# altimeter.net
KiCad netlist of a schematic drawn in EAGLE
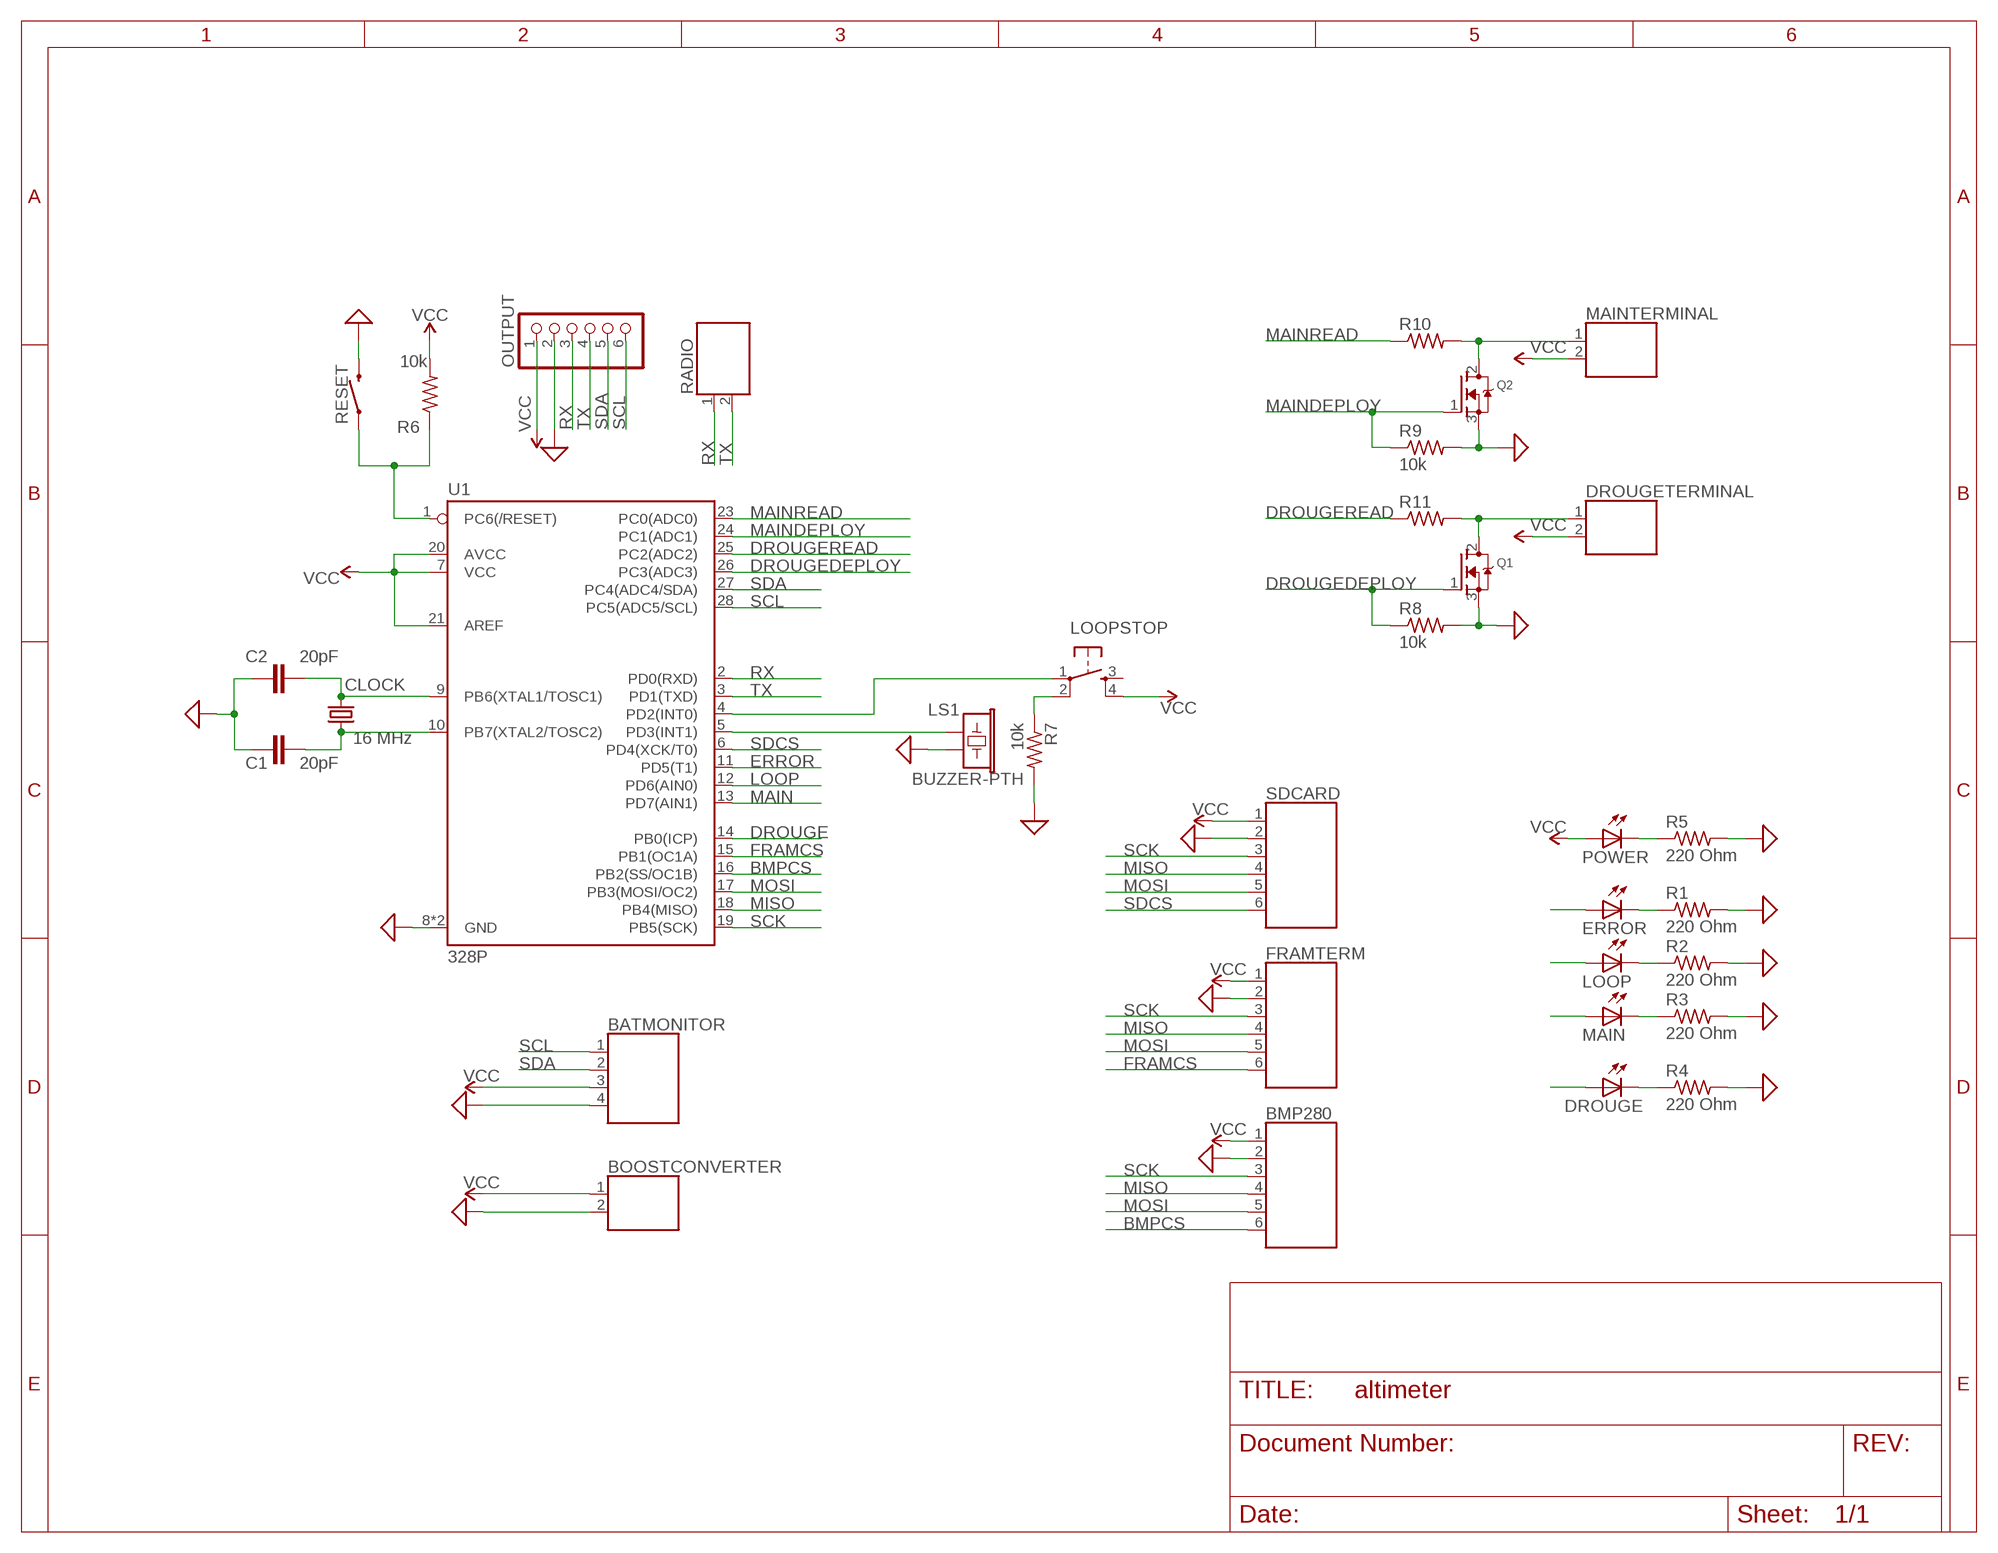
[diagram p0: schematic, sheet 1]

(export (version "E")
  (design (tool "Eeschema 10.0.6"))
  (components
    (comp (ref "BATMONITOR")
      (value "691386700004")
      (footprint "eagle-import:691386700004")
      (libsource (lib "eagle-import") (part "691386700004"))
    )
    (comp (ref "BMP280")
      (value "691386700006")
      (footprint "eagle-import:691386700006")
      (libsource (lib "eagle-import") (part "691386700006"))
    )
    (comp (ref "BOOSTCONVERTER")
      (value "691386700002")
      (footprint "eagle-import:691386700002")
      (libsource (lib "eagle-import") (part "691386700002"))
    )
    (comp (ref "C1")
      (value "20pF")
      (footprint "eagle-import:CAP-PTH-2.54")
      (fields (field (name "SPICEPREFIX") "C"))
      (libsource (lib "eagle-import") (part "22PF-PTH-2.54MM-200V-5%"))
    )
    (comp (ref "C2")
      (value "20pF")
      (footprint "eagle-import:CAP-PTH-2.54")
      (fields (field (name "SPICEPREFIX") "C"))
      (libsource (lib "eagle-import") (part "22PF-PTH-2.54MM-200V-5%"))
    )
    (comp (ref "CLOCK")
      (value "16 MHz")
      (footprint "eagle-import:HC49U-V")
      (fields (field (name "SPICEPREFIX") "C"))
      (libsource (lib "eagle-import") (part "CRYSTALHC49U-V"))
    )
    (comp (ref "DROUGE")
      (value "LED5MM")
      (footprint "eagle-import:LED5MM")
      (libsource (lib "eagle-import") (part "LED5MM"))
    )
    (comp (ref "DROUGETERMINAL")
      (value "691386700002")
      (footprint "eagle-import:691386700002")
      (libsource (lib "eagle-import") (part "691386700002"))
    )
    (comp (ref "ERROR")
      (value "LED5MM")
      (footprint "eagle-import:LED5MM")
      (libsource (lib "eagle-import") (part "LED5MM"))
    )
    (comp (ref "FRAMTERM")
      (value "691386700006")
      (footprint "eagle-import:691386700006")
      (libsource (lib "eagle-import") (part "691386700006"))
    )
    (comp (ref "LOOP")
      (value "LED5MM")
      (footprint "eagle-import:LED5MM")
      (libsource (lib "eagle-import") (part "LED5MM"))
    )
    (comp (ref "LOOPSTOP")
      (value "TAC_SWITCHPTH")
      (footprint "eagle-import:TACTILE-PTH")
      (libsource (lib "eagle-import") (part "TAC_SWITCHPTH"))
    )
    (comp (ref "LS1")
      (value "BUZZER-PTH")
      (footprint "eagle-import:BUZZER-12MM")
      (libsource (lib "eagle-import") (part "BUZZER-PTH"))
    )
    (comp (ref "MAIN")
      (value "LED5MM")
      (footprint "eagle-import:LED5MM")
      (libsource (lib "eagle-import") (part "LED5MM"))
    )
    (comp (ref "MAINTERMINAL")
      (value "691386700002")
      (footprint "eagle-import:691386700002")
      (libsource (lib "eagle-import") (part "691386700002"))
    )
    (comp (ref "OUTPUT")
      (value "PINHD-1X6")
      (footprint "eagle-import:1X06")
      (libsource (lib "eagle-import") (part "PINHD-1X6"))
    )
    (comp (ref "POWER")
      (value "LED5MM")
      (footprint "eagle-import:LED5MM")
      (libsource (lib "eagle-import") (part "LED5MM"))
    )
    (comp (ref "Q1")
      (value "MOSFET-NGDS_TO220V")
      (footprint "eagle-import:TO220V")
      (libsource (lib "eagle-import") (part "MOSFET-NGDS_TO220V"))
    )
    (comp (ref "Q2")
      (value "MOSFET-NGDS_TO220V")
      (footprint "eagle-import:TO220V")
      (libsource (lib "eagle-import") (part "MOSFET-NGDS_TO220V"))
    )
    (comp (ref "R1")
      (value "220 Ohm")
      (footprint "eagle-import:0204_7")
      (libsource (lib "eagle-import") (part "R-US_0204/7"))
    )
    (comp (ref "R2")
      (value "220 Ohm")
      (footprint "eagle-import:0204_7")
      (libsource (lib "eagle-import") (part "R-US_0204/7"))
    )
    (comp (ref "R3")
      (value "220 Ohm")
      (footprint "eagle-import:0204_7")
      (libsource (lib "eagle-import") (part "R-US_0204/7"))
    )
    (comp (ref "R4")
      (value "220 Ohm")
      (footprint "eagle-import:0204_7")
      (libsource (lib "eagle-import") (part "R-US_0204/7"))
    )
    (comp (ref "R5")
      (value "220 Ohm")
      (footprint "eagle-import:0204_7")
      (libsource (lib "eagle-import") (part "R-US_0204/7"))
    )
    (comp (ref "R6")
      (value "10k")
      (footprint "eagle-import:0204_7")
      (libsource (lib "eagle-import") (part "R-US_0204/7"))
    )
    (comp (ref "R7")
      (value "10k")
      (footprint "eagle-import:0204_7")
      (libsource (lib "eagle-import") (part "R-US_0204/7"))
    )
    (comp (ref "R8")
      (value "10k")
      (footprint "eagle-import:0204_7")
      (libsource (lib "eagle-import") (part "R-US_0204/7"))
    )
    (comp (ref "R9")
      (value "10k")
      (footprint "eagle-import:0204_7")
      (libsource (lib "eagle-import") (part "R-US_0204/7"))
    )
    (comp (ref "R10")
      (value "R-US_0204/7")
      (footprint "eagle-import:0204_7")
      (libsource (lib "eagle-import") (part "R-US_0204/7"))
    )
    (comp (ref "R11")
      (value "R-US_0204/7")
      (footprint "eagle-import:0204_7")
      (libsource (lib "eagle-import") (part "R-US_0204/7"))
    )
    (comp (ref "RADIO")
      (value "691386700002")
      (footprint "eagle-import:691386700002")
      (libsource (lib "eagle-import") (part "691386700002"))
    )
    (comp (ref "RESET")
      (value "MOMENTARY-SWITCH-SPST-PTH-6.0MM")
      (footprint "eagle-import:TACTILE_SWITCH_PTH_6.0MM")
      (libsource (lib "eagle-import") (part "MOMENTARY-SWITCH-SPST-PTH-6.0MM"))
    )
    (comp (ref "SDCARD")
      (value "691386700006")
      (footprint "eagle-import:691386700006")
      (libsource (lib "eagle-import") (part "691386700006"))
    )
    (comp (ref "U1")
      (value "328P")
      (footprint "eagle-import:DIP28")
      (libsource (lib "eagle-import") (part "ATMEGA328P_PDIP"))
    )
  )
  (nets
    (net (code "1") (name "/BMPCS") (class "Default")
      (node (ref "BMP280") (pin "6") (pinfunction "6_6") (pintype "passive"))
      (node (ref "U1") (pin "16") (pinfunction "PB2(SS/OC1B)_16") (pintype "bidirectional"))
    )
    (net (code "2") (name "/DROUGE") (class "Default")
      (node (ref "DROUGE") (pin "A") (pinfunction "A_A") (pintype "passive"))
      (node (ref "U1") (pin "14") (pinfunction "PB0(ICP)_14") (pintype "bidirectional"))
    )
    (net (code "3") (name "/DROUGEDEPLOY") (class "Default")
      (node (ref "Q1") (pin "1") (pinfunction "G_1") (pintype "bidirectional"))
      (node (ref "R8") (pin "1") (pinfunction "1_1") (pintype "passive"))
      (node (ref "U1") (pin "26") (pinfunction "PC3(ADC3)_26") (pintype "bidirectional"))
    )
    (net (code "4") (name "/DROUGEREAD") (class "Default")
      (node (ref "R11") (pin "1") (pinfunction "1_1") (pintype "passive"))
      (node (ref "U1") (pin "25") (pinfunction "PC2(ADC2)_25") (pintype "bidirectional"))
    )
    (net (code "5") (name "/ERROR") (class "Default")
      (node (ref "ERROR") (pin "A") (pinfunction "A_A") (pintype "passive"))
      (node (ref "U1") (pin "11") (pinfunction "PD5(T1)_11") (pintype "bidirectional"))
    )
    (net (code "6") (name "/FRAMCS") (class "Default")
      (node (ref "FRAMTERM") (pin "6") (pinfunction "6_6") (pintype "passive"))
      (node (ref "U1") (pin "15") (pinfunction "PB1(OC1A)_15") (pintype "bidirectional"))
    )
    (net (code "7") (name "/LOOP") (class "Default")
      (node (ref "LOOP") (pin "A") (pinfunction "A_A") (pintype "passive"))
      (node (ref "U1") (pin "12") (pinfunction "PD6(AIN0)_12") (pintype "bidirectional"))
    )
    (net (code "8") (name "/MAIN") (class "Default")
      (node (ref "MAIN") (pin "A") (pinfunction "A_A") (pintype "passive"))
      (node (ref "U1") (pin "13") (pinfunction "PD7(AIN1)_13") (pintype "bidirectional"))
    )
    (net (code "9") (name "/MAINDEPLOY") (class "Default")
      (node (ref "Q2") (pin "1") (pinfunction "G_1") (pintype "bidirectional"))
      (node (ref "R9") (pin "1") (pinfunction "1_1") (pintype "passive"))
      (node (ref "U1") (pin "24") (pinfunction "PC1(ADC1)_24") (pintype "bidirectional"))
    )
    (net (code "10") (name "/MAINREAD") (class "Default")
      (node (ref "R10") (pin "1") (pinfunction "1_1") (pintype "passive"))
      (node (ref "U1") (pin "23") (pinfunction "PC0(ADC0)_23") (pintype "bidirectional"))
    )
    (net (code "11") (name "/MISO") (class "Default")
      (node (ref "BMP280") (pin "4") (pinfunction "4_4") (pintype "passive"))
      (node (ref "FRAMTERM") (pin "4") (pinfunction "4_4") (pintype "passive"))
      (node (ref "SDCARD") (pin "4") (pinfunction "4_4") (pintype "passive"))
      (node (ref "U1") (pin "18") (pinfunction "PB4(MISO)_18") (pintype "bidirectional"))
    )
    (net (code "12") (name "/MOSI") (class "Default")
      (node (ref "BMP280") (pin "5") (pinfunction "5_5") (pintype "passive"))
      (node (ref "FRAMTERM") (pin "5") (pinfunction "5_5") (pintype "passive"))
      (node (ref "SDCARD") (pin "5") (pinfunction "5_5") (pintype "passive"))
      (node (ref "U1") (pin "17") (pinfunction "PB3(MOSI/OC2)_17") (pintype "bidirectional"))
    )
    (net (code "13") (name "/RX") (class "Default")
      (node (ref "OUTPUT") (pin "3") (pinfunction "3_3") (pintype "passive"))
      (node (ref "RADIO") (pin "1") (pinfunction "1_1") (pintype "passive"))
      (node (ref "U1") (pin "2") (pinfunction "PD0(RXD)_2") (pintype "bidirectional"))
    )
    (net (code "14") (name "/SCK") (class "Default")
      (node (ref "BMP280") (pin "3") (pinfunction "3_3") (pintype "passive"))
      (node (ref "FRAMTERM") (pin "3") (pinfunction "3_3") (pintype "passive"))
      (node (ref "SDCARD") (pin "3") (pinfunction "3_3") (pintype "passive"))
      (node (ref "U1") (pin "19") (pinfunction "PB5(SCK)_19") (pintype "bidirectional"))
    )
    (net (code "15") (name "/SCL") (class "Default")
      (node (ref "BATMONITOR") (pin "1") (pinfunction "1_1") (pintype "passive"))
      (node (ref "OUTPUT") (pin "6") (pinfunction "6_6") (pintype "passive"))
      (node (ref "U1") (pin "28") (pinfunction "PC5(ADC5/SCL)_28") (pintype "bidirectional"))
    )
    (net (code "16") (name "/SDA") (class "Default")
      (node (ref "BATMONITOR") (pin "2") (pinfunction "2_2") (pintype "passive"))
      (node (ref "OUTPUT") (pin "5") (pinfunction "5_5") (pintype "passive"))
      (node (ref "U1") (pin "27") (pinfunction "PC4(ADC4/SDA)_27") (pintype "bidirectional"))
    )
    (net (code "17") (name "/SDCS") (class "Default")
      (node (ref "SDCARD") (pin "6") (pinfunction "6_6") (pintype "passive"))
      (node (ref "U1") (pin "6") (pinfunction "PD4(XCK/T0)_6") (pintype "bidirectional"))
    )
    (net (code "18") (name "/TX") (class "Default")
      (node (ref "OUTPUT") (pin "4") (pinfunction "4_4") (pintype "passive"))
      (node (ref "RADIO") (pin "2") (pinfunction "2_2") (pintype "passive"))
      (node (ref "U1") (pin "3") (pinfunction "PD1(TXD)_3") (pintype "bidirectional"))
    )
    (net (code "19") (name "Net-(DROUGE-C)") (class "Default")
      (node (ref "DROUGE") (pin "K") (pinfunction "C_K") (pintype "passive"))
      (node (ref "R4") (pin "1") (pinfunction "1_1") (pintype "passive"))
    )
    (net (code "20") (name "Net-(ERROR-C)") (class "Default")
      (node (ref "ERROR") (pin "K") (pinfunction "C_K") (pintype "passive"))
      (node (ref "R1") (pin "1") (pinfunction "1_1") (pintype "passive"))
    )
    (net (code "21") (name "Net-(LOOP-C)") (class "Default")
      (node (ref "LOOP") (pin "K") (pinfunction "C_K") (pintype "passive"))
      (node (ref "R2") (pin "1") (pinfunction "1_1") (pintype "passive"))
    )
    (net (code "22") (name "Net-(LOOPSTOP-Pad2)") (class "Default")
      (node (ref "LOOPSTOP") (pin "2") (pinfunction "2_2") (pintype "passive"))
      (node (ref "R7") (pin "1") (pinfunction "1_1") (pintype "passive"))
    )
    (net (code "23") (name "Net-(LS1-1)") (class "Default")
      (node (ref "LS1") (pin "+") (pinfunction "1_+") (pintype "passive"))
      (node (ref "U1") (pin "5") (pinfunction "PD3(INT1)_5") (pintype "bidirectional"))
    )
    (net (code "24") (name "Net-(MAIN-C)") (class "Default")
      (node (ref "MAIN") (pin "K") (pinfunction "C_K") (pintype "passive"))
      (node (ref "R3") (pin "1") (pinfunction "1_1") (pintype "passive"))
    )
    (net (code "25") (name "Net-(POWER-C)") (class "Default")
      (node (ref "POWER") (pin "K") (pinfunction "C_K") (pintype "passive"))
      (node (ref "R5") (pin "1") (pinfunction "1_1") (pintype "passive"))
    )
    (net (code "26") (name "Net-(Q1-D)") (class "Default")
      (node (ref "DROUGETERMINAL") (pin "1") (pinfunction "1_1") (pintype "passive"))
      (node (ref "Q1") (pin "2") (pinfunction "D_2") (pintype "bidirectional"))
      (node (ref "R11") (pin "2") (pinfunction "2_2") (pintype "passive"))
    )
    (net (code "27") (name "Net-(Q2-D)") (class "Default")
      (node (ref "MAINTERMINAL") (pin "1") (pinfunction "1_1") (pintype "passive"))
      (node (ref "Q2") (pin "2") (pinfunction "D_2") (pintype "bidirectional"))
      (node (ref "R10") (pin "2") (pinfunction "2_2") (pintype "passive"))
    )
    (net (code "28") (name "Net-(U1-PB6(XTAL1{slash}TOSC1))") (class "Default")
      (node (ref "C2") (pin "2") (pinfunction "2_2") (pintype "passive"))
      (node (ref "CLOCK") (pin "2") (pinfunction "2_2") (pintype "passive"))
      (node (ref "U1") (pin "9") (pinfunction "PB6(XTAL1/TOSC1)_9") (pintype "bidirectional"))
    )
    (net (code "29") (name "Net-(U1-PB7(XTAL2{slash}TOSC2))") (class "Default")
      (node (ref "C1") (pin "2") (pinfunction "2_2") (pintype "passive"))
      (node (ref "CLOCK") (pin "1") (pinfunction "1_1") (pintype "passive"))
      (node (ref "U1") (pin "10") (pinfunction "PB7(XTAL2/TOSC2)_10") (pintype "bidirectional"))
    )
    (net (code "30") (name "Net-(U1-PC6({slash}RESET))") (class "Default")
      (node (ref "R6") (pin "1") (pinfunction "1_1") (pintype "passive"))
      (node (ref "RESET") (pin "1") (pinfunction "1_1") (pintype "passive"))
      (node (ref "U1") (pin "1") (pinfunction "PC6(/RESET)_1") (pintype "bidirectional"))
    )
    (net (code "31") (name "Net-(U1-PD2(INT0))") (class "Default")
      (node (ref "LOOPSTOP") (pin "1") (pinfunction "1_1") (pintype "passive"))
      (node (ref "U1") (pin "4") (pinfunction "PD2(INT0)_4") (pintype "bidirectional"))
    )
    (net (code "32") (name "SUP") (class "Default")
      (node (ref "BATMONITOR") (pin "4") (pinfunction "4_4") (pintype "passive"))
      (node (ref "BMP280") (pin "2") (pinfunction "2_2") (pintype "passive"))
      (node (ref "BOOSTCONVERTER") (pin "2") (pinfunction "2_2") (pintype "passive"))
      (node (ref "C1") (pin "1") (pinfunction "1_1") (pintype "passive"))
      (node (ref "C2") (pin "1") (pinfunction "1_1") (pintype "passive"))
      (node (ref "FRAMTERM") (pin "2") (pinfunction "2_2") (pintype "passive"))
      (node (ref "LS1") (pin "-") (pinfunction "2_-") (pintype "passive"))
      (node (ref "OUTPUT") (pin "2") (pinfunction "2_2") (pintype "passive"))
      (node (ref "Q1") (pin "3") (pinfunction "S_3") (pintype "bidirectional"))
      (node (ref "Q2") (pin "3") (pinfunction "S_3") (pintype "bidirectional"))
      (node (ref "R1") (pin "2") (pinfunction "2_2") (pintype "passive"))
      (node (ref "R2") (pin "2") (pinfunction "2_2") (pintype "passive"))
      (node (ref "R3") (pin "2") (pinfunction "2_2") (pintype "passive"))
      (node (ref "R4") (pin "2") (pinfunction "2_2") (pintype "passive"))
      (node (ref "R5") (pin "2") (pinfunction "2_2") (pintype "passive"))
      (node (ref "R7") (pin "2") (pinfunction "2_2") (pintype "passive"))
      (node (ref "R8") (pin "2") (pinfunction "2_2") (pintype "passive"))
      (node (ref "R9") (pin "2") (pinfunction "2_2") (pintype "passive"))
      (node (ref "RESET") (pin "3") (pinfunction "2_3") (pintype "passive"))
      (node (ref "SDCARD") (pin "2") (pinfunction "2_2") (pintype "passive"))
      (node (ref "U1") (pin "22") (pinfunction "GND_22") (pintype "bidirectional"))
      (node (ref "U1") (pin "8") (pinfunction "GND_8") (pintype "bidirectional"))
    )
    (net (code "33") (name "VCC") (class "Default")
      (node (ref "BATMONITOR") (pin "3") (pinfunction "3_3") (pintype "passive"))
      (node (ref "BMP280") (pin "1") (pinfunction "1_1") (pintype "passive"))
      (node (ref "BOOSTCONVERTER") (pin "1") (pinfunction "1_1") (pintype "passive"))
      (node (ref "DROUGETERMINAL") (pin "2") (pinfunction "2_2") (pintype "passive"))
      (node (ref "FRAMTERM") (pin "1") (pinfunction "1_1") (pintype "passive"))
      (node (ref "LOOPSTOP") (pin "4") (pinfunction "4_4") (pintype "passive"))
      (node (ref "MAINTERMINAL") (pin "2") (pinfunction "2_2") (pintype "passive"))
      (node (ref "OUTPUT") (pin "1") (pinfunction "1_1") (pintype "passive"))
      (node (ref "POWER") (pin "A") (pinfunction "A_A") (pintype "passive"))
      (node (ref "R6") (pin "2") (pinfunction "2_2") (pintype "passive"))
      (node (ref "SDCARD") (pin "1") (pinfunction "1_1") (pintype "passive"))
      (node (ref "U1") (pin "20") (pinfunction "AVCC_20") (pintype "bidirectional"))
      (node (ref "U1") (pin "21") (pinfunction "AREF_21") (pintype "bidirectional"))
      (node (ref "U1") (pin "7") (pinfunction "VCC_7") (pintype "bidirectional"))
    )
    (net (code "34") (name "unconnected-(LOOPSTOP-Pad3)") (class "Default")
      (node (ref "LOOPSTOP") (pin "3") (pinfunction "3_3") (pintype "passive"))
    )
  )
)
